# AKLM-1_4.net
KiCad netlist of a schematic drawn in EAGLE
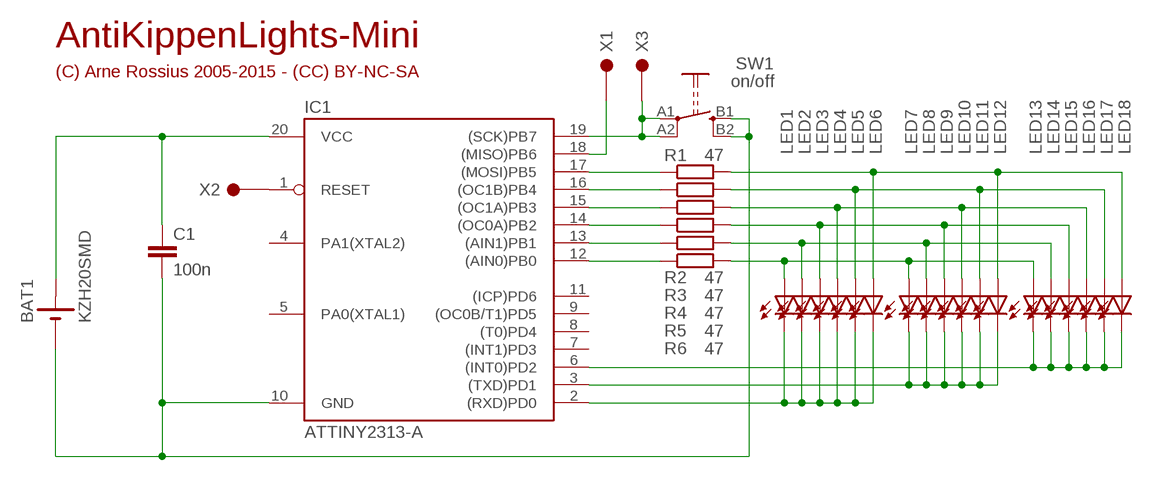
[diagram p0: schematic, sheet 1]

(export (version "E")
  (design (tool "Eeschema 10.0.6"))
  (components
    (comp (ref "BAT1")
      (value "KZH20SMD")
      (footprint "eagle-import:KZH20SMD")
      (libsource (lib "eagle-import") (part "KZH20SMD"))
    )
    (comp (ref "C1")
      (value "100n")
      (footprint "eagle-import:C0805")
      (libsource (lib "eagle-import") (part "C-EUC0805"))
    )
    (comp (ref "IC1")
      (value "ATTINY2313-A")
      (footprint "eagle-import:SO20W")
      (libsource (lib "eagle-import") (part "ATTINY2313-A"))
    )
    (comp (ref "LED1")
      (value "LED_0805")
      (footprint "eagle-import:CHIPLED_0805")
      (libsource (lib "eagle-import") (part "LED_0805"))
    )
    (comp (ref "LED2")
      (value "LED_0805")
      (footprint "eagle-import:CHIPLED_0805")
      (libsource (lib "eagle-import") (part "LED_0805"))
    )
    (comp (ref "LED3")
      (value "LED_0805")
      (footprint "eagle-import:CHIPLED_0805")
      (libsource (lib "eagle-import") (part "LED_0805"))
    )
    (comp (ref "LED4")
      (value "LED_0805")
      (footprint "eagle-import:CHIPLED_0805")
      (libsource (lib "eagle-import") (part "LED_0805"))
    )
    (comp (ref "LED5")
      (value "LED_0805")
      (footprint "eagle-import:CHIPLED_0805")
      (libsource (lib "eagle-import") (part "LED_0805"))
    )
    (comp (ref "LED6")
      (value "LED_0805")
      (footprint "eagle-import:CHIPLED_0805")
      (libsource (lib "eagle-import") (part "LED_0805"))
    )
    (comp (ref "LED7")
      (value "LED_0805")
      (footprint "eagle-import:CHIPLED_0805")
      (libsource (lib "eagle-import") (part "LED_0805"))
    )
    (comp (ref "LED8")
      (value "LED_0805")
      (footprint "eagle-import:CHIPLED_0805")
      (libsource (lib "eagle-import") (part "LED_0805"))
    )
    (comp (ref "LED9")
      (value "LED_0805")
      (footprint "eagle-import:CHIPLED_0805")
      (libsource (lib "eagle-import") (part "LED_0805"))
    )
    (comp (ref "LED10")
      (value "LED_0805")
      (footprint "eagle-import:CHIPLED_0805")
      (libsource (lib "eagle-import") (part "LED_0805"))
    )
    (comp (ref "LED11")
      (value "LED_0805")
      (footprint "eagle-import:CHIPLED_0805")
      (libsource (lib "eagle-import") (part "LED_0805"))
    )
    (comp (ref "LED12")
      (value "LED_0805")
      (footprint "eagle-import:CHIPLED_0805")
      (libsource (lib "eagle-import") (part "LED_0805"))
    )
    (comp (ref "LED13")
      (value "LED_0805")
      (footprint "eagle-import:CHIPLED_0805")
      (libsource (lib "eagle-import") (part "LED_0805"))
    )
    (comp (ref "LED14")
      (value "LED_0805")
      (footprint "eagle-import:CHIPLED_0805")
      (libsource (lib "eagle-import") (part "LED_0805"))
    )
    (comp (ref "LED15")
      (value "LED_0805")
      (footprint "eagle-import:CHIPLED_0805")
      (libsource (lib "eagle-import") (part "LED_0805"))
    )
    (comp (ref "LED16")
      (value "LED_0805")
      (footprint "eagle-import:CHIPLED_0805")
      (libsource (lib "eagle-import") (part "LED_0805"))
    )
    (comp (ref "LED17")
      (value "LED_0805")
      (footprint "eagle-import:CHIPLED_0805")
      (libsource (lib "eagle-import") (part "LED_0805"))
    )
    (comp (ref "LED18")
      (value "LED_0805")
      (footprint "eagle-import:CHIPLED_0805")
      (libsource (lib "eagle-import") (part "LED_0805"))
    )
    (comp (ref "R1")
      (value "47")
      (footprint "eagle-import:R0805")
      (libsource (lib "eagle-import") (part "R-EU_R0805"))
    )
    (comp (ref "R2")
      (value "47")
      (footprint "eagle-import:R0805")
      (libsource (lib "eagle-import") (part "R-EU_R0805"))
    )
    (comp (ref "R3")
      (value "47")
      (footprint "eagle-import:R0805")
      (libsource (lib "eagle-import") (part "R-EU_R0805"))
    )
    (comp (ref "R4")
      (value "47")
      (footprint "eagle-import:R0805")
      (libsource (lib "eagle-import") (part "R-EU_R0805"))
    )
    (comp (ref "R5")
      (value "47")
      (footprint "eagle-import:R0805")
      (libsource (lib "eagle-import") (part "R-EU_R0805"))
    )
    (comp (ref "R6")
      (value "47")
      (footprint "eagle-import:R0805")
      (libsource (lib "eagle-import") (part "R-EU_R0805"))
    )
    (comp (ref "SW1")
      (value "on/off")
      (footprint "eagle-import:LSG-KEY")
      (libsource (lib "eagle-import") (part "LSG_KEY_(SCHURTER)"))
    )
    (comp (ref "X1")
      (value "SMDPAD-75")
      (footprint "eagle-import:SMDPAD_75MIL")
      (libsource (lib "eagle-import") (part "SMDPAD-75"))
    )
    (comp (ref "X2")
      (value "SMDPAD-75")
      (footprint "eagle-import:SMDPAD_75MIL")
      (libsource (lib "eagle-import") (part "SMDPAD-75"))
    )
    (comp (ref "X3")
      (value "SMDPAD-75")
      (footprint "eagle-import:SMDPAD_75MIL")
      (libsource (lib "eagle-import") (part "SMDPAD-75"))
    )
  )
  (nets
    (net (code "1") (name "Net-(BAT1-+)") (class "Default")
      (node (ref "BAT1") (pin "POS") (pinfunction "+_POS") (pintype "power_in"))
      (node (ref "C1") (pin "1") (pinfunction "1_1") (pintype "passive"))
      (node (ref "IC1") (pin "20") (pinfunction "VCC_20") (pintype "power_in"))
    )
    (net (code "2") (name "Net-(BAT1--)") (class "Default")
      (node (ref "BAT1") (pin "NEG") (pinfunction "-_NEG") (pintype "power_in"))
      (node (ref "C1") (pin "2") (pinfunction "2_2") (pintype "passive"))
      (node (ref "IC1") (pin "10") (pinfunction "GND_10") (pintype "power_in"))
      (node (ref "SW1") (pin "B1") (pinfunction "S_B1") (pintype "passive"))
      (node (ref "SW1") (pin "B2") (pinfunction "S_B2") (pintype "passive"))
    )
    (net (code "3") (name "Net-(IC1-(AIN0)PB0)") (class "Default")
      (node (ref "IC1") (pin "12") (pinfunction "(AIN0)PB0_12") (pintype "bidirectional"))
      (node (ref "R6") (pin "1") (pinfunction "1_1") (pintype "passive"))
    )
    (net (code "4") (name "Net-(IC1-(AIN1)PB1)") (class "Default")
      (node (ref "IC1") (pin "13") (pinfunction "(AIN1)PB1_13") (pintype "bidirectional"))
      (node (ref "R5") (pin "1") (pinfunction "1_1") (pintype "passive"))
    )
    (net (code "5") (name "Net-(IC1-(INT0)PD2)") (class "Default")
      (node (ref "IC1") (pin "6") (pinfunction "(INT0)PD2_6") (pintype "bidirectional"))
      (node (ref "LED13") (pin "C") (pinfunction "C_C") (pintype "passive"))
      (node (ref "LED14") (pin "C") (pinfunction "C_C") (pintype "passive"))
      (node (ref "LED15") (pin "C") (pinfunction "C_C") (pintype "passive"))
      (node (ref "LED16") (pin "C") (pinfunction "C_C") (pintype "passive"))
      (node (ref "LED17") (pin "C") (pinfunction "C_C") (pintype "passive"))
      (node (ref "LED18") (pin "C") (pinfunction "C_C") (pintype "passive"))
    )
    (net (code "6") (name "Net-(IC1-(MISO)PB6)") (class "Default")
      (node (ref "IC1") (pin "18") (pinfunction "(MISO)PB6_18") (pintype "bidirectional"))
      (node (ref "X1") (pin "PAD") (pinfunction "P$1_PAD") (pintype "bidirectional"))
    )
    (net (code "7") (name "Net-(IC1-(MOSI)PB5)") (class "Default")
      (node (ref "IC1") (pin "17") (pinfunction "(MOSI)PB5_17") (pintype "bidirectional"))
      (node (ref "R1") (pin "1") (pinfunction "1_1") (pintype "passive"))
    )
    (net (code "8") (name "Net-(IC1-(OC0A)PB2)") (class "Default")
      (node (ref "IC1") (pin "14") (pinfunction "(OC0A)PB2_14") (pintype "bidirectional"))
      (node (ref "R4") (pin "1") (pinfunction "1_1") (pintype "passive"))
    )
    (net (code "9") (name "Net-(IC1-(OC1A)PB3)") (class "Default")
      (node (ref "IC1") (pin "15") (pinfunction "(OC1A)PB3_15") (pintype "bidirectional"))
      (node (ref "R3") (pin "1") (pinfunction "1_1") (pintype "passive"))
    )
    (net (code "10") (name "Net-(IC1-(OC1B)PB4)") (class "Default")
      (node (ref "IC1") (pin "16") (pinfunction "(OC1B)PB4_16") (pintype "bidirectional"))
      (node (ref "R2") (pin "1") (pinfunction "1_1") (pintype "passive"))
    )
    (net (code "11") (name "Net-(IC1-(RXD)PD0)") (class "Default")
      (node (ref "IC1") (pin "2") (pinfunction "(RXD)PD0_2") (pintype "bidirectional"))
      (node (ref "LED1") (pin "C") (pinfunction "C_C") (pintype "passive"))
      (node (ref "LED2") (pin "C") (pinfunction "C_C") (pintype "passive"))
      (node (ref "LED3") (pin "C") (pinfunction "C_C") (pintype "passive"))
      (node (ref "LED4") (pin "C") (pinfunction "C_C") (pintype "passive"))
      (node (ref "LED5") (pin "C") (pinfunction "C_C") (pintype "passive"))
      (node (ref "LED6") (pin "C") (pinfunction "C_C") (pintype "passive"))
    )
    (net (code "12") (name "Net-(IC1-(SCK)PB7)") (class "Default")
      (node (ref "IC1") (pin "19") (pinfunction "(SCK)PB7_19") (pintype "bidirectional"))
      (node (ref "SW1") (pin "A1") (pinfunction "P_A1") (pintype "passive"))
      (node (ref "SW1") (pin "A2") (pinfunction "P_A2") (pintype "passive"))
      (node (ref "X3") (pin "PAD") (pinfunction "P$1_PAD") (pintype "bidirectional"))
    )
    (net (code "13") (name "Net-(IC1-(TXD)PD1)") (class "Default")
      (node (ref "IC1") (pin "3") (pinfunction "(TXD)PD1_3") (pintype "bidirectional"))
      (node (ref "LED10") (pin "C") (pinfunction "C_C") (pintype "passive"))
      (node (ref "LED11") (pin "C") (pinfunction "C_C") (pintype "passive"))
      (node (ref "LED12") (pin "C") (pinfunction "C_C") (pintype "passive"))
      (node (ref "LED7") (pin "C") (pinfunction "C_C") (pintype "passive"))
      (node (ref "LED8") (pin "C") (pinfunction "C_C") (pintype "passive"))
      (node (ref "LED9") (pin "C") (pinfunction "C_C") (pintype "passive"))
    )
    (net (code "14") (name "Net-(IC1-RESET)") (class "Default")
      (node (ref "IC1") (pin "1") (pinfunction "RESET_1") (pintype "bidirectional"))
      (node (ref "X2") (pin "PAD") (pinfunction "P$1_PAD") (pintype "bidirectional"))
    )
    (net (code "15") (name "Net-(LED1-PadA)") (class "Default")
      (node (ref "LED1") (pin "A") (pinfunction "A_A") (pintype "passive"))
      (node (ref "LED13") (pin "A") (pinfunction "A_A") (pintype "passive"))
      (node (ref "LED7") (pin "A") (pinfunction "A_A") (pintype "passive"))
      (node (ref "R6") (pin "2") (pinfunction "2_2") (pintype "passive"))
    )
    (net (code "16") (name "Net-(LED10-PadA)") (class "Default")
      (node (ref "LED10") (pin "A") (pinfunction "A_A") (pintype "passive"))
      (node (ref "LED16") (pin "A") (pinfunction "A_A") (pintype "passive"))
      (node (ref "LED4") (pin "A") (pinfunction "A_A") (pintype "passive"))
      (node (ref "R3") (pin "2") (pinfunction "2_2") (pintype "passive"))
    )
    (net (code "17") (name "Net-(LED11-PadA)") (class "Default")
      (node (ref "LED11") (pin "A") (pinfunction "A_A") (pintype "passive"))
      (node (ref "LED17") (pin "A") (pinfunction "A_A") (pintype "passive"))
      (node (ref "LED5") (pin "A") (pinfunction "A_A") (pintype "passive"))
      (node (ref "R2") (pin "2") (pinfunction "2_2") (pintype "passive"))
    )
    (net (code "18") (name "Net-(LED12-PadA)") (class "Default")
      (node (ref "LED12") (pin "A") (pinfunction "A_A") (pintype "passive"))
      (node (ref "LED18") (pin "A") (pinfunction "A_A") (pintype "passive"))
      (node (ref "LED6") (pin "A") (pinfunction "A_A") (pintype "passive"))
      (node (ref "R1") (pin "2") (pinfunction "2_2") (pintype "passive"))
    )
    (net (code "19") (name "Net-(LED14-PadA)") (class "Default")
      (node (ref "LED14") (pin "A") (pinfunction "A_A") (pintype "passive"))
      (node (ref "LED2") (pin "A") (pinfunction "A_A") (pintype "passive"))
      (node (ref "LED8") (pin "A") (pinfunction "A_A") (pintype "passive"))
      (node (ref "R5") (pin "2") (pinfunction "2_2") (pintype "passive"))
    )
    (net (code "20") (name "Net-(LED15-PadA)") (class "Default")
      (node (ref "LED15") (pin "A") (pinfunction "A_A") (pintype "passive"))
      (node (ref "LED3") (pin "A") (pinfunction "A_A") (pintype "passive"))
      (node (ref "LED9") (pin "A") (pinfunction "A_A") (pintype "passive"))
      (node (ref "R4") (pin "2") (pinfunction "2_2") (pintype "passive"))
    )
    (net (code "21") (name "unconnected-(IC1-(ICP)PD6-Pad11)") (class "Default")
      (node (ref "IC1") (pin "11") (pinfunction "(ICP)PD6_11") (pintype "bidirectional"))
    )
    (net (code "22") (name "unconnected-(IC1-(INT1)PD3-Pad7)") (class "Default")
      (node (ref "IC1") (pin "7") (pinfunction "(INT1)PD3_7") (pintype "bidirectional"))
    )
    (net (code "23") (name "unconnected-(IC1-(OC0B{slash}T1)PD5-Pad9)") (class "Default")
      (node (ref "IC1") (pin "9") (pinfunction "(OC0B/T1)PD5_9") (pintype "bidirectional"))
    )
    (net (code "24") (name "unconnected-(IC1-(T0)PD4-Pad8)") (class "Default")
      (node (ref "IC1") (pin "8") (pinfunction "(T0)PD4_8") (pintype "bidirectional"))
    )
    (net (code "25") (name "unconnected-(IC1-PA0(XTAL1)-Pad5)") (class "Default")
      (node (ref "IC1") (pin "5") (pinfunction "PA0(XTAL1)_5") (pintype "bidirectional"))
    )
    (net (code "26") (name "unconnected-(IC1-PA1(XTAL2)-Pad4)") (class "Default")
      (node (ref "IC1") (pin "4") (pinfunction "PA1(XTAL2)_4") (pintype "bidirectional"))
    )
  )
)
